# programmer.net
KiCad netlist of a schematic drawn in EAGLE
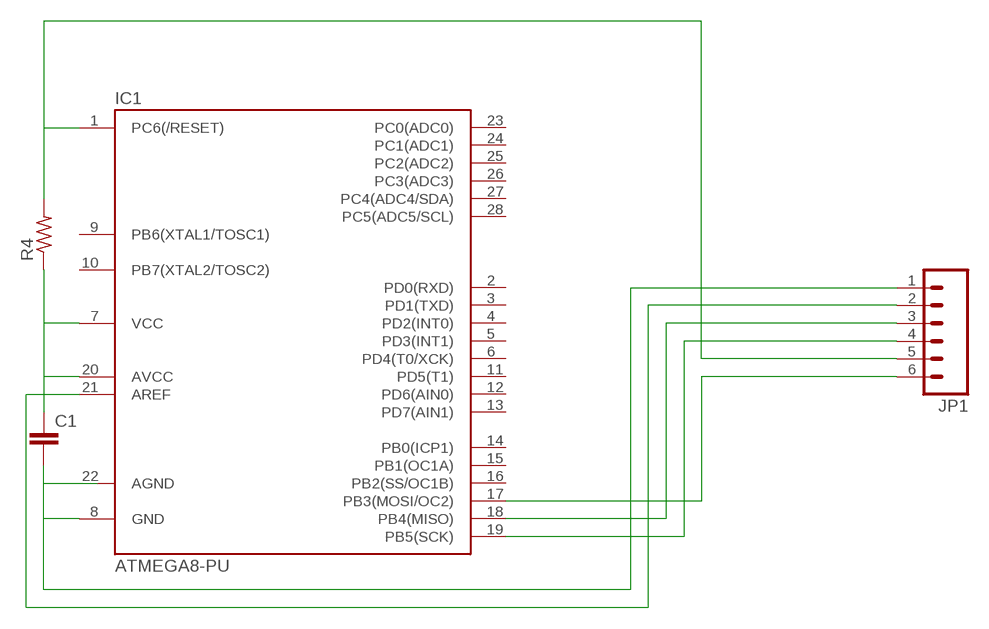
[diagram p0: schematic, sheet 1]

(export (version "E")
  (design (tool "Eeschema 10.0.6"))
  (components
    (comp (ref "C1")
      (value "C2.5/4")
      (footprint "eagle-import:C2.5-4")
      (libsource (lib "eagle-import") (part "C2.5/4"))
    )
    (comp (ref "IC1")
      (value "ATMEGA8-PU")
      (footprint "eagle-import:DIL28-3")
      (libsource (lib "eagle-import") (part "ATMEGA8-PU"))
    )
    (comp (ref "JP1")
      (value "M06LONGPADS")
      (footprint "eagle-import:1X06_LONGPADS")
      (libsource (lib "eagle-import") (part "M06LONGPADS"))
    )
    (comp (ref "R4")
      (value "R-US_0207/12")
      (footprint "eagle-import:0207_12")
      (libsource (lib "eagle-import") (part "R-US_0207/12"))
    )
  )
  (nets
    (net (code "1") (name "/AGND") (class "Default")
      (node (ref "IC1") (pin "22") (pinfunction "AGND_22") (pintype "power_in"))
    )
    (net (code "2") (name "Net-(IC1-AREF)") (class "Default")
      (node (ref "C1") (pin "1") (pinfunction "1_1") (pintype "passive"))
      (node (ref "IC1") (pin "21") (pinfunction "AREF_21") (pintype "passive"))
      (node (ref "IC1") (pin "7") (pinfunction "VCC_7") (pintype "power_in"))
      (node (ref "JP1") (pin "2") (pinfunction "2_2") (pintype "passive"))
      (node (ref "R4") (pin "1") (pinfunction "1_1") (pintype "passive"))
    )
    (net (code "3") (name "Net-(IC1-GND)") (class "Default")
      (node (ref "C1") (pin "2") (pinfunction "2_2") (pintype "passive"))
      (node (ref "IC1") (pin "8") (pinfunction "GND_8") (pintype "power_in"))
      (node (ref "JP1") (pin "1") (pinfunction "1_1") (pintype "passive"))
    )
    (net (code "4") (name "Net-(IC1-PB3(MOSI{slash}OC2))") (class "Default")
      (node (ref "IC1") (pin "17") (pinfunction "PB3(MOSI/OC2)_17") (pintype "bidirectional"))
      (node (ref "JP1") (pin "6") (pinfunction "6_6") (pintype "passive"))
    )
    (net (code "5") (name "Net-(IC1-PB4(MISO))") (class "Default")
      (node (ref "IC1") (pin "18") (pinfunction "PB4(MISO)_18") (pintype "bidirectional"))
      (node (ref "JP1") (pin "3") (pinfunction "3_3") (pintype "passive"))
    )
    (net (code "6") (name "Net-(IC1-PB5(SCK))") (class "Default")
      (node (ref "IC1") (pin "19") (pinfunction "PB5(SCK)_19") (pintype "bidirectional"))
      (node (ref "JP1") (pin "4") (pinfunction "4_4") (pintype "passive"))
    )
    (net (code "7") (name "Net-(IC1-PC6({slash}RESET))") (class "Default")
      (node (ref "IC1") (pin "1") (pinfunction "PC6(/RESET)_1") (pintype "bidirectional"))
      (node (ref "JP1") (pin "5") (pinfunction "5_5") (pintype "passive"))
      (node (ref "R4") (pin "2") (pinfunction "2_2") (pintype "passive"))
    )
    (net (code "8") (name "unconnected-(IC1-AVCC-Pad20)") (class "Default")
      (node (ref "IC1") (pin "20") (pinfunction "AVCC_20") (pintype "passive"))
    )
    (net (code "9") (name "unconnected-(IC1-PB0(ICP1)-Pad14)") (class "Default")
      (node (ref "IC1") (pin "14") (pinfunction "PB0(ICP1)_14") (pintype "bidirectional"))
    )
    (net (code "10") (name "unconnected-(IC1-PB1(OC1A)-Pad15)") (class "Default")
      (node (ref "IC1") (pin "15") (pinfunction "PB1(OC1A)_15") (pintype "bidirectional"))
    )
    (net (code "11") (name "unconnected-(IC1-PB2(SS{slash}OC1B)-Pad16)") (class "Default")
      (node (ref "IC1") (pin "16") (pinfunction "PB2(SS/OC1B)_16") (pintype "bidirectional"))
    )
    (net (code "12") (name "unconnected-(IC1-PB6(XTAL1{slash}TOSC1)-Pad9)") (class "Default")
      (node (ref "IC1") (pin "9") (pinfunction "PB6(XTAL1/TOSC1)_9") (pintype "bidirectional"))
    )
    (net (code "13") (name "unconnected-(IC1-PB7(XTAL2{slash}TOSC2)-Pad10)") (class "Default")
      (node (ref "IC1") (pin "10") (pinfunction "PB7(XTAL2/TOSC2)_10") (pintype "bidirectional"))
    )
    (net (code "14") (name "unconnected-(IC1-PC0(ADC0)-Pad23)") (class "Default")
      (node (ref "IC1") (pin "23") (pinfunction "PC0(ADC0)_23") (pintype "bidirectional"))
    )
    (net (code "15") (name "unconnected-(IC1-PC1(ADC1)-Pad24)") (class "Default")
      (node (ref "IC1") (pin "24") (pinfunction "PC1(ADC1)_24") (pintype "bidirectional"))
    )
    (net (code "16") (name "unconnected-(IC1-PC2(ADC2)-Pad25)") (class "Default")
      (node (ref "IC1") (pin "25") (pinfunction "PC2(ADC2)_25") (pintype "bidirectional"))
    )
    (net (code "17") (name "unconnected-(IC1-PC3(ADC3)-Pad26)") (class "Default")
      (node (ref "IC1") (pin "26") (pinfunction "PC3(ADC3)_26") (pintype "bidirectional"))
    )
    (net (code "18") (name "unconnected-(IC1-PC4(ADC4{slash}SDA)-Pad27)") (class "Default")
      (node (ref "IC1") (pin "27") (pinfunction "PC4(ADC4/SDA)_27") (pintype "bidirectional"))
    )
    (net (code "19") (name "unconnected-(IC1-PC5(ADC5{slash}SCL)-Pad28)") (class "Default")
      (node (ref "IC1") (pin "28") (pinfunction "PC5(ADC5/SCL)_28") (pintype "bidirectional"))
    )
    (net (code "20") (name "unconnected-(IC1-PD0(RXD)-Pad2)") (class "Default")
      (node (ref "IC1") (pin "2") (pinfunction "PD0(RXD)_2") (pintype "bidirectional"))
    )
    (net (code "21") (name "unconnected-(IC1-PD1(TXD)-Pad3)") (class "Default")
      (node (ref "IC1") (pin "3") (pinfunction "PD1(TXD)_3") (pintype "bidirectional"))
    )
    (net (code "22") (name "unconnected-(IC1-PD2(INT0)-Pad4)") (class "Default")
      (node (ref "IC1") (pin "4") (pinfunction "PD2(INT0)_4") (pintype "bidirectional"))
    )
    (net (code "23") (name "unconnected-(IC1-PD3(INT1)-Pad5)") (class "Default")
      (node (ref "IC1") (pin "5") (pinfunction "PD3(INT1)_5") (pintype "bidirectional"))
    )
    (net (code "24") (name "unconnected-(IC1-PD4(T0{slash}XCK)-Pad6)") (class "Default")
      (node (ref "IC1") (pin "6") (pinfunction "PD4(T0/XCK)_6") (pintype "bidirectional"))
    )
    (net (code "25") (name "unconnected-(IC1-PD5(T1)-Pad11)") (class "Default")
      (node (ref "IC1") (pin "11") (pinfunction "PD5(T1)_11") (pintype "bidirectional"))
    )
    (net (code "26") (name "unconnected-(IC1-PD6(AIN0)-Pad12)") (class "Default")
      (node (ref "IC1") (pin "12") (pinfunction "PD6(AIN0)_12") (pintype "bidirectional"))
    )
    (net (code "27") (name "unconnected-(IC1-PD7(AIN1)-Pad13)") (class "Default")
      (node (ref "IC1") (pin "13") (pinfunction "PD7(AIN1)_13") (pintype "bidirectional"))
    )
  )
)
